# DEPTHAI_CAM_INTERFACE.net
KiCad netlist of a schematic drawn in Altium Designer
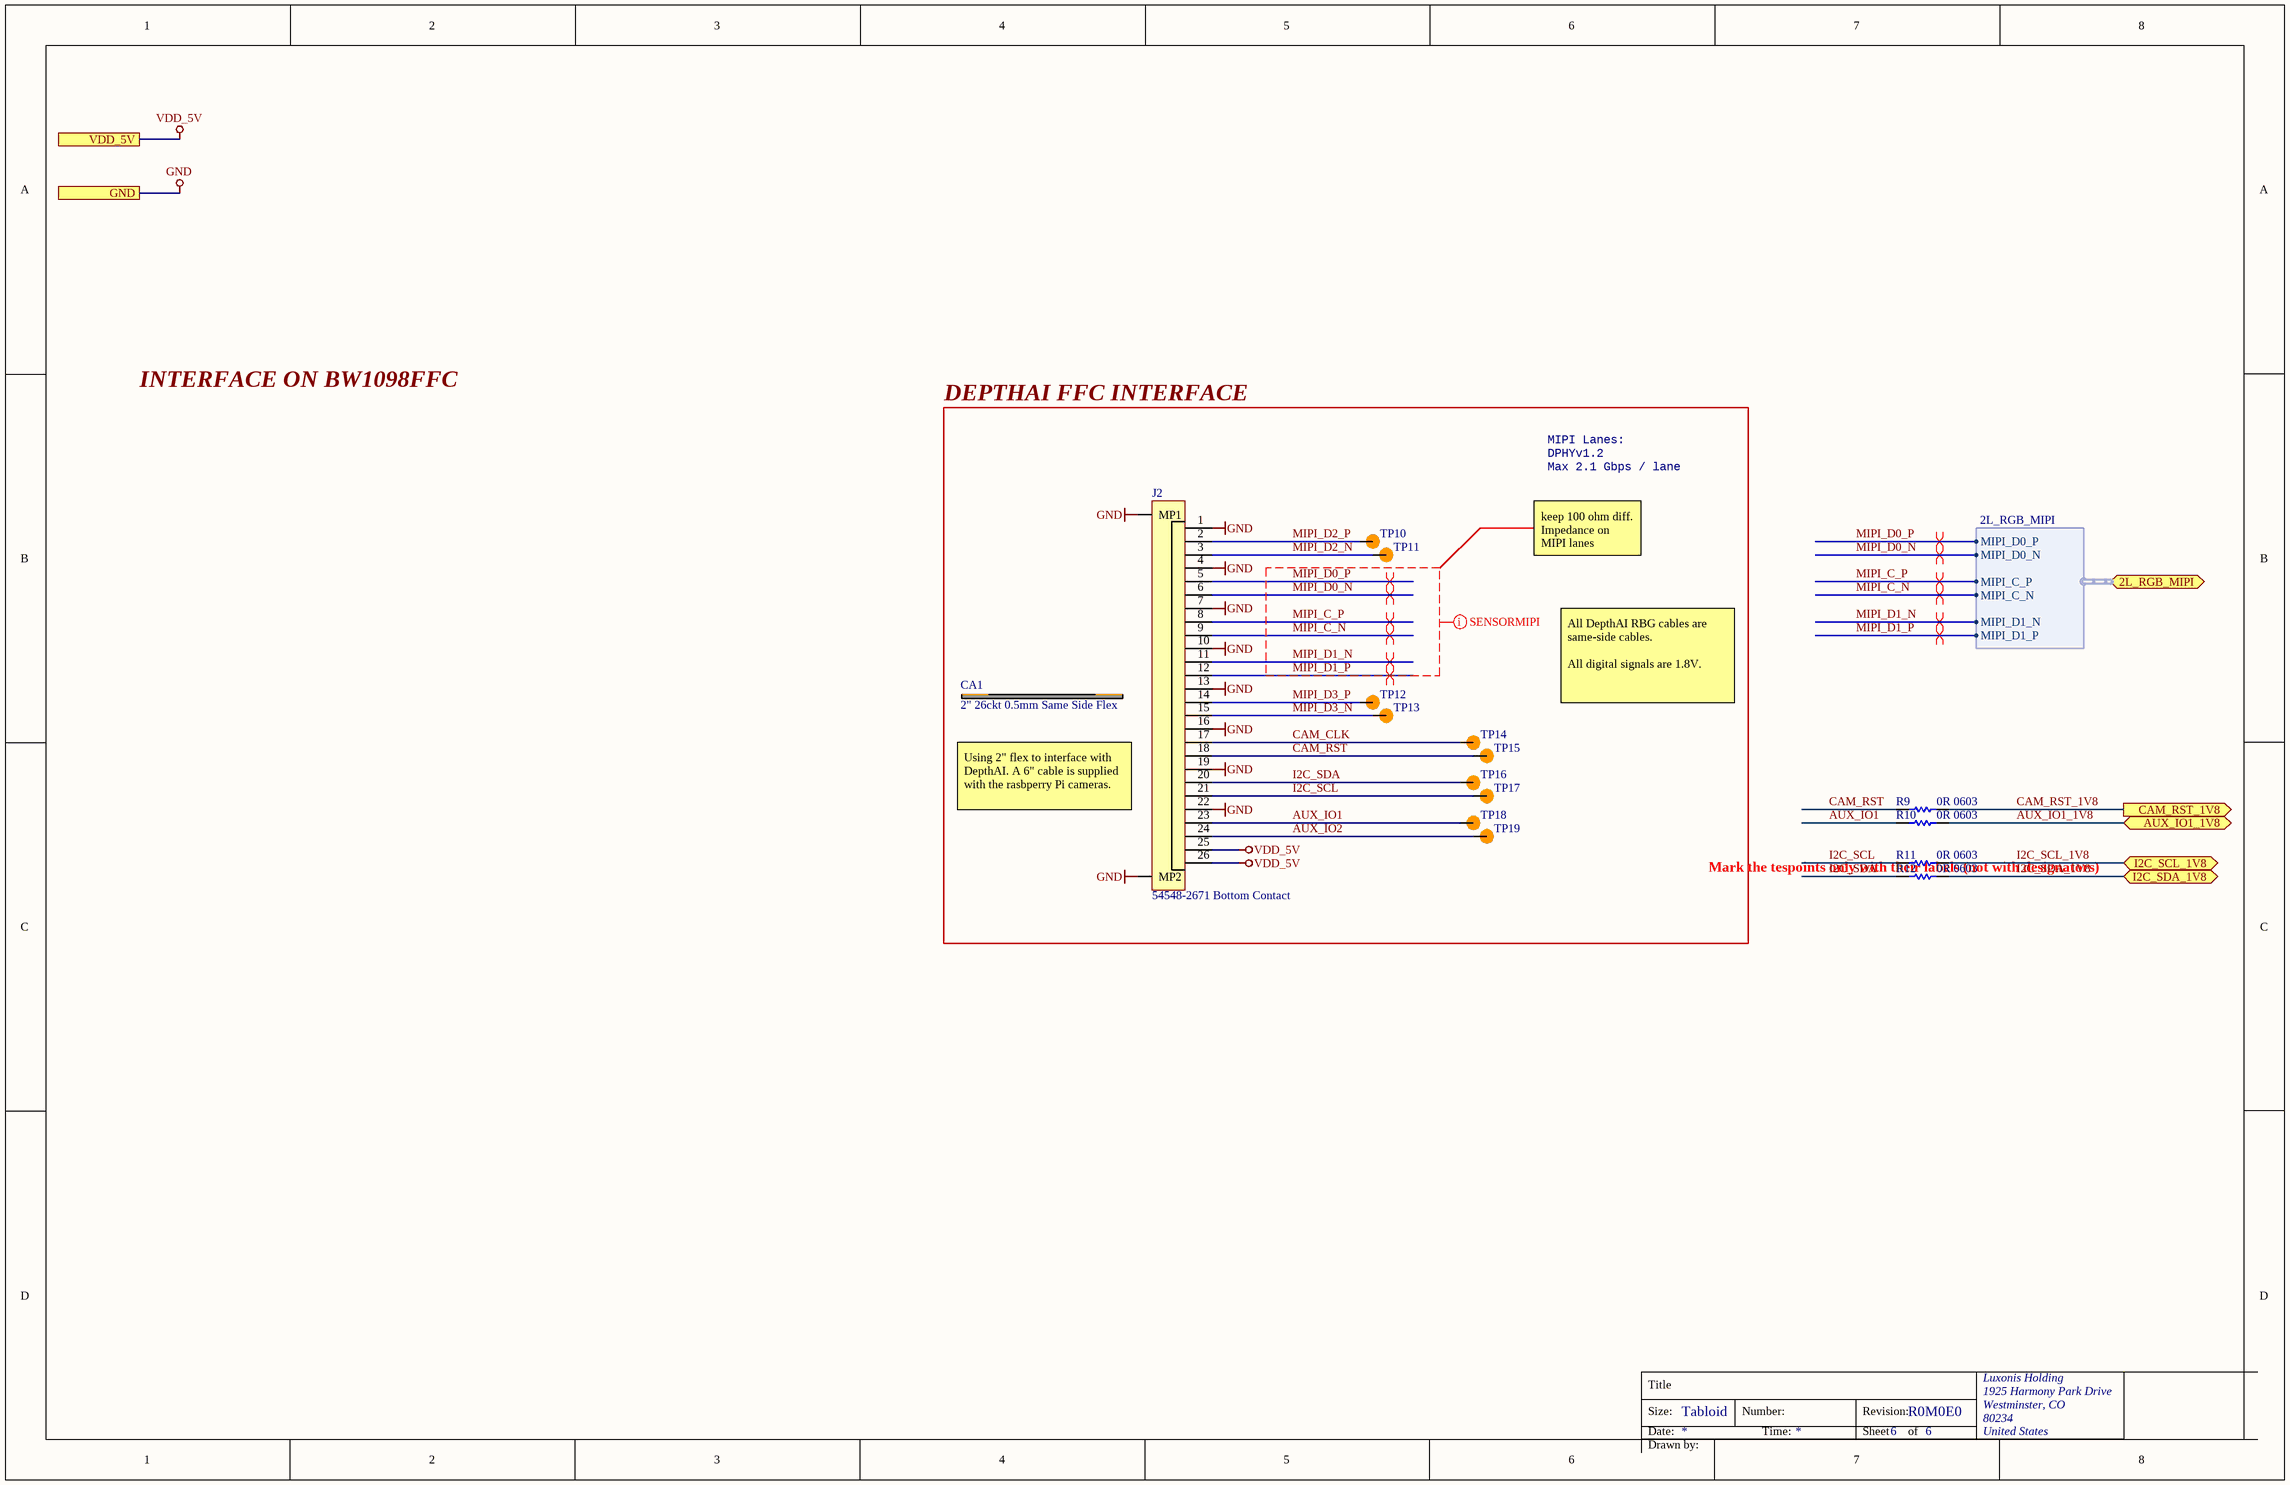
[diagram p0: DEPTHAI_CAM_INTERFACE.SchDoc]

(export (version "E")
  (design (tool "Eeschema 10.0.6"))
  (components
    (comp (ref "CA1")
      (value "2\" 26ckt 0.5mm Same Side Flex")
      (description "FFC 0.50 TYPE A 26 CKTS LGT 51")
      (libsource (lib "BW0253_R0M0E0") (part "0151660273"))
    )
    (comp (ref "J2")
      (value "54548-2671 Bottom Contact")
      (footprint "LuxonisMaster:54548-2671")
      (fields
        (field (name "MANUFACTURER_PART_NUMBER") "54548-2671")
        (field (name "MOUSER PART NUMBER") "538-54548-2671")
      )
      (libsource (lib "LuxonisMaster") (part "54548-2671"))
    )
    (comp (ref "R9")
      (value "0R 0603")
      (footprint "RES_Altium_Vault_Generic:RESC0603(1608)_M")
      (fields (field (name "TOLERANCE") "5%"))
      (libsource (lib "LuxonisMaster") (part "CRCW06030000Z0EA"))
    )
    (comp (ref "R10")
      (value "0R 0603")
      (footprint "RES_Altium_Vault_Generic:RESC0603(1608)_M")
      (fields (field (name "TOLERANCE") "5%"))
      (libsource (lib "LuxonisMaster") (part "CRCW06030000Z0EA"))
    )
    (comp (ref "R11")
      (value "0R 0603")
      (footprint "RES_Altium_Vault_Generic:RESC0603(1608)_M")
      (fields (field (name "TOLERANCE") "5%"))
      (libsource (lib "LuxonisMaster") (part "CRCW06030000Z0EA"))
    )
    (comp (ref "R12")
      (value "0R 0603")
      (footprint "RES_Altium_Vault_Generic:RESC0603(1608)_M")
      (fields (field (name "TOLERANCE") "5%"))
      (libsource (lib "LuxonisMaster") (part "CRCW06030000Z0EA"))
    )
    (comp (ref "TP10")
      (value "TP075_150_NS")
      (footprint "LuxonisMaster:TP075_150_NS")
      (libsource (lib "LuxonisMaster") (part "TEST_POINT"))
    )
    (comp (ref "TP11")
      (value "TP075_150_NS")
      (footprint "LuxonisMaster:TP075_150_NS")
      (libsource (lib "LuxonisMaster") (part "TEST_POINT"))
    )
    (comp (ref "TP12")
      (value "TP075_150_NS")
      (footprint "LuxonisMaster:TP075_150_NS")
      (libsource (lib "LuxonisMaster") (part "TEST_POINT"))
    )
    (comp (ref "TP13")
      (value "TP075_150_NS")
      (footprint "LuxonisMaster:TP075_150_NS")
      (libsource (lib "LuxonisMaster") (part "TEST_POINT"))
    )
    (comp (ref "TP14")
      (value "TP100_150_NS")
      (footprint "LuxonisMaster:TP100_150_NS")
      (libsource (lib "LuxonisMaster") (part "TEST_POINT"))
    )
    (comp (ref "TP15")
      (value "TP100_150_NS")
      (footprint "LuxonisMaster:TP100_150_NS")
      (libsource (lib "LuxonisMaster") (part "TEST_POINT"))
    )
    (comp (ref "TP16")
      (value "TP100_150_NS")
      (footprint "LuxonisMaster:TP100_150_NS")
      (libsource (lib "LuxonisMaster") (part "TEST_POINT"))
    )
    (comp (ref "TP17")
      (value "TP100_150_NS")
      (footprint "LuxonisMaster:TP100_150_NS")
      (libsource (lib "LuxonisMaster") (part "TEST_POINT"))
    )
    (comp (ref "TP18")
      (value "TP100_150_NS")
      (footprint "LuxonisMaster:TP100_150_NS")
      (libsource (lib "LuxonisMaster") (part "TEST_POINT"))
    )
    (comp (ref "TP19")
      (value "TP100_150_NS")
      (footprint "LuxonisMaster:TP100_150_NS")
      (libsource (lib "LuxonisMaster") (part "TEST_POINT"))
    )
  )
  (nets
    (net (code "2") (name "/AUX_IO1") (class "Default")
      (node (ref "J2") (pin "23") (pinfunction "23_23") (pintype "passive"))
      (node (ref "R10") (pin "1") (pinfunction "1_1") (pintype "passive"))
      (node (ref "TP18") (pin "1") (pintype "passive"))
    )
    (net (code "3") (name "/AUX_IO1_1V8") (class "Default")
      (node (ref "R10") (pin "2") (pinfunction "2_2") (pintype "passive"))
    )
    (net (code "4") (name "/AUX_IO2") (class "Default")
      (node (ref "J2") (pin "24") (pinfunction "24_24") (pintype "passive"))
      (node (ref "TP19") (pin "1") (pintype "passive"))
    )
    (net (code "5") (name "/CAM_CLK") (class "Default")
      (node (ref "J2") (pin "17") (pinfunction "17_17") (pintype "passive"))
      (node (ref "TP14") (pin "1") (pintype "passive"))
    )
    (net (code "6") (name "/CAM_RST") (class "Default")
      (node (ref "J2") (pin "18") (pinfunction "18_18") (pintype "passive"))
      (node (ref "R9") (pin "1") (pinfunction "1_1") (pintype "passive"))
      (node (ref "TP15") (pin "1") (pintype "passive"))
    )
    (net (code "7") (name "/CAM_RST_1V8") (class "Default")
      (node (ref "R9") (pin "2") (pinfunction "2_2") (pintype "passive"))
    )
    (net (code "8") (name "/I2C_SCL") (class "Default")
      (node (ref "J2") (pin "21") (pinfunction "21_21") (pintype "passive"))
      (node (ref "R11") (pin "1") (pinfunction "1_1") (pintype "passive"))
      (node (ref "TP17") (pin "1") (pintype "passive"))
    )
    (net (code "9") (name "/I2C_SCL_1V8") (class "Default")
      (node (ref "R11") (pin "2") (pinfunction "2_2") (pintype "passive"))
    )
    (net (code "10") (name "/I2C_SDA") (class "Default")
      (node (ref "J2") (pin "20") (pinfunction "20_20") (pintype "passive"))
      (node (ref "R12") (pin "1") (pinfunction "1_1") (pintype "passive"))
      (node (ref "TP16") (pin "1") (pintype "passive"))
    )
    (net (code "11") (name "/I2C_SDA_1V8") (class "Default")
      (node (ref "R12") (pin "2") (pinfunction "2_2") (pintype "passive"))
    )
    (net (code "12") (name "/MIPI_C_N") (class "Default")
      (node (ref "J2") (pin "9") (pinfunction "9_9") (pintype "passive"))
    )
    (net (code "13") (name "/MIPI_C_P") (class "Default")
      (node (ref "J2") (pin "8") (pinfunction "8_8") (pintype "passive"))
    )
    (net (code "14") (name "/MIPI_D0_N") (class "Default")
      (node (ref "J2") (pin "6") (pinfunction "6_6") (pintype "passive"))
    )
    (net (code "15") (name "/MIPI_D0_P") (class "Default")
      (node (ref "J2") (pin "5") (pinfunction "5_5") (pintype "passive"))
    )
    (net (code "16") (name "/MIPI_D1_N") (class "Default")
      (node (ref "J2") (pin "11") (pinfunction "11_11") (pintype "passive"))
    )
    (net (code "17") (name "/MIPI_D1_P") (class "Default")
      (node (ref "J2") (pin "12") (pinfunction "12_12") (pintype "passive"))
    )
    (net (code "18") (name "/MIPI_D2_N") (class "Default")
      (node (ref "J2") (pin "3") (pinfunction "3_3") (pintype "passive"))
      (node (ref "TP11") (pin "1") (pintype "passive"))
    )
    (net (code "19") (name "/MIPI_D2_P") (class "Default")
      (node (ref "J2") (pin "2") (pinfunction "2_2") (pintype "passive"))
      (node (ref "TP10") (pin "1") (pintype "passive"))
    )
    (net (code "20") (name "/MIPI_D3_N") (class "Default")
      (node (ref "J2") (pin "15") (pinfunction "15_15") (pintype "passive"))
      (node (ref "TP13") (pin "1") (pintype "passive"))
    )
    (net (code "21") (name "/MIPI_D3_P") (class "Default")
      (node (ref "J2") (pin "14") (pinfunction "14_14") (pintype "passive"))
      (node (ref "TP12") (pin "1") (pintype "passive"))
    )
    (net (code "23") (name "GND") (class "Default")
      (node (ref "J2") (pin "1") (pinfunction "1_1") (pintype "passive"))
      (node (ref "J2") (pin "10") (pinfunction "10_10") (pintype "passive"))
      (node (ref "J2") (pin "13") (pinfunction "13_13") (pintype "passive"))
      (node (ref "J2") (pin "16") (pinfunction "16_16") (pintype "passive"))
      (node (ref "J2") (pin "19") (pinfunction "19_19") (pintype "passive"))
      (node (ref "J2") (pin "22") (pinfunction "22_22") (pintype "passive"))
      (node (ref "J2") (pin "4") (pinfunction "4_4") (pintype "passive"))
      (node (ref "J2") (pin "7") (pinfunction "7_7") (pintype "passive"))
      (node (ref "J2") (pin "MP1") (pinfunction "MP1_MP1") (pintype "passive"))
      (node (ref "J2") (pin "MP2") (pinfunction "MP2_MP2") (pintype "passive"))
    )
    (net (code "24") (name "VDD_5V") (class "Default")
      (node (ref "J2") (pin "25") (pinfunction "25_25") (pintype "passive"))
      (node (ref "J2") (pin "26") (pinfunction "26_26") (pintype "passive"))
    )
  )
)
